# memory_mkII.net
KiCad netlist of a schematic drawn in EAGLE
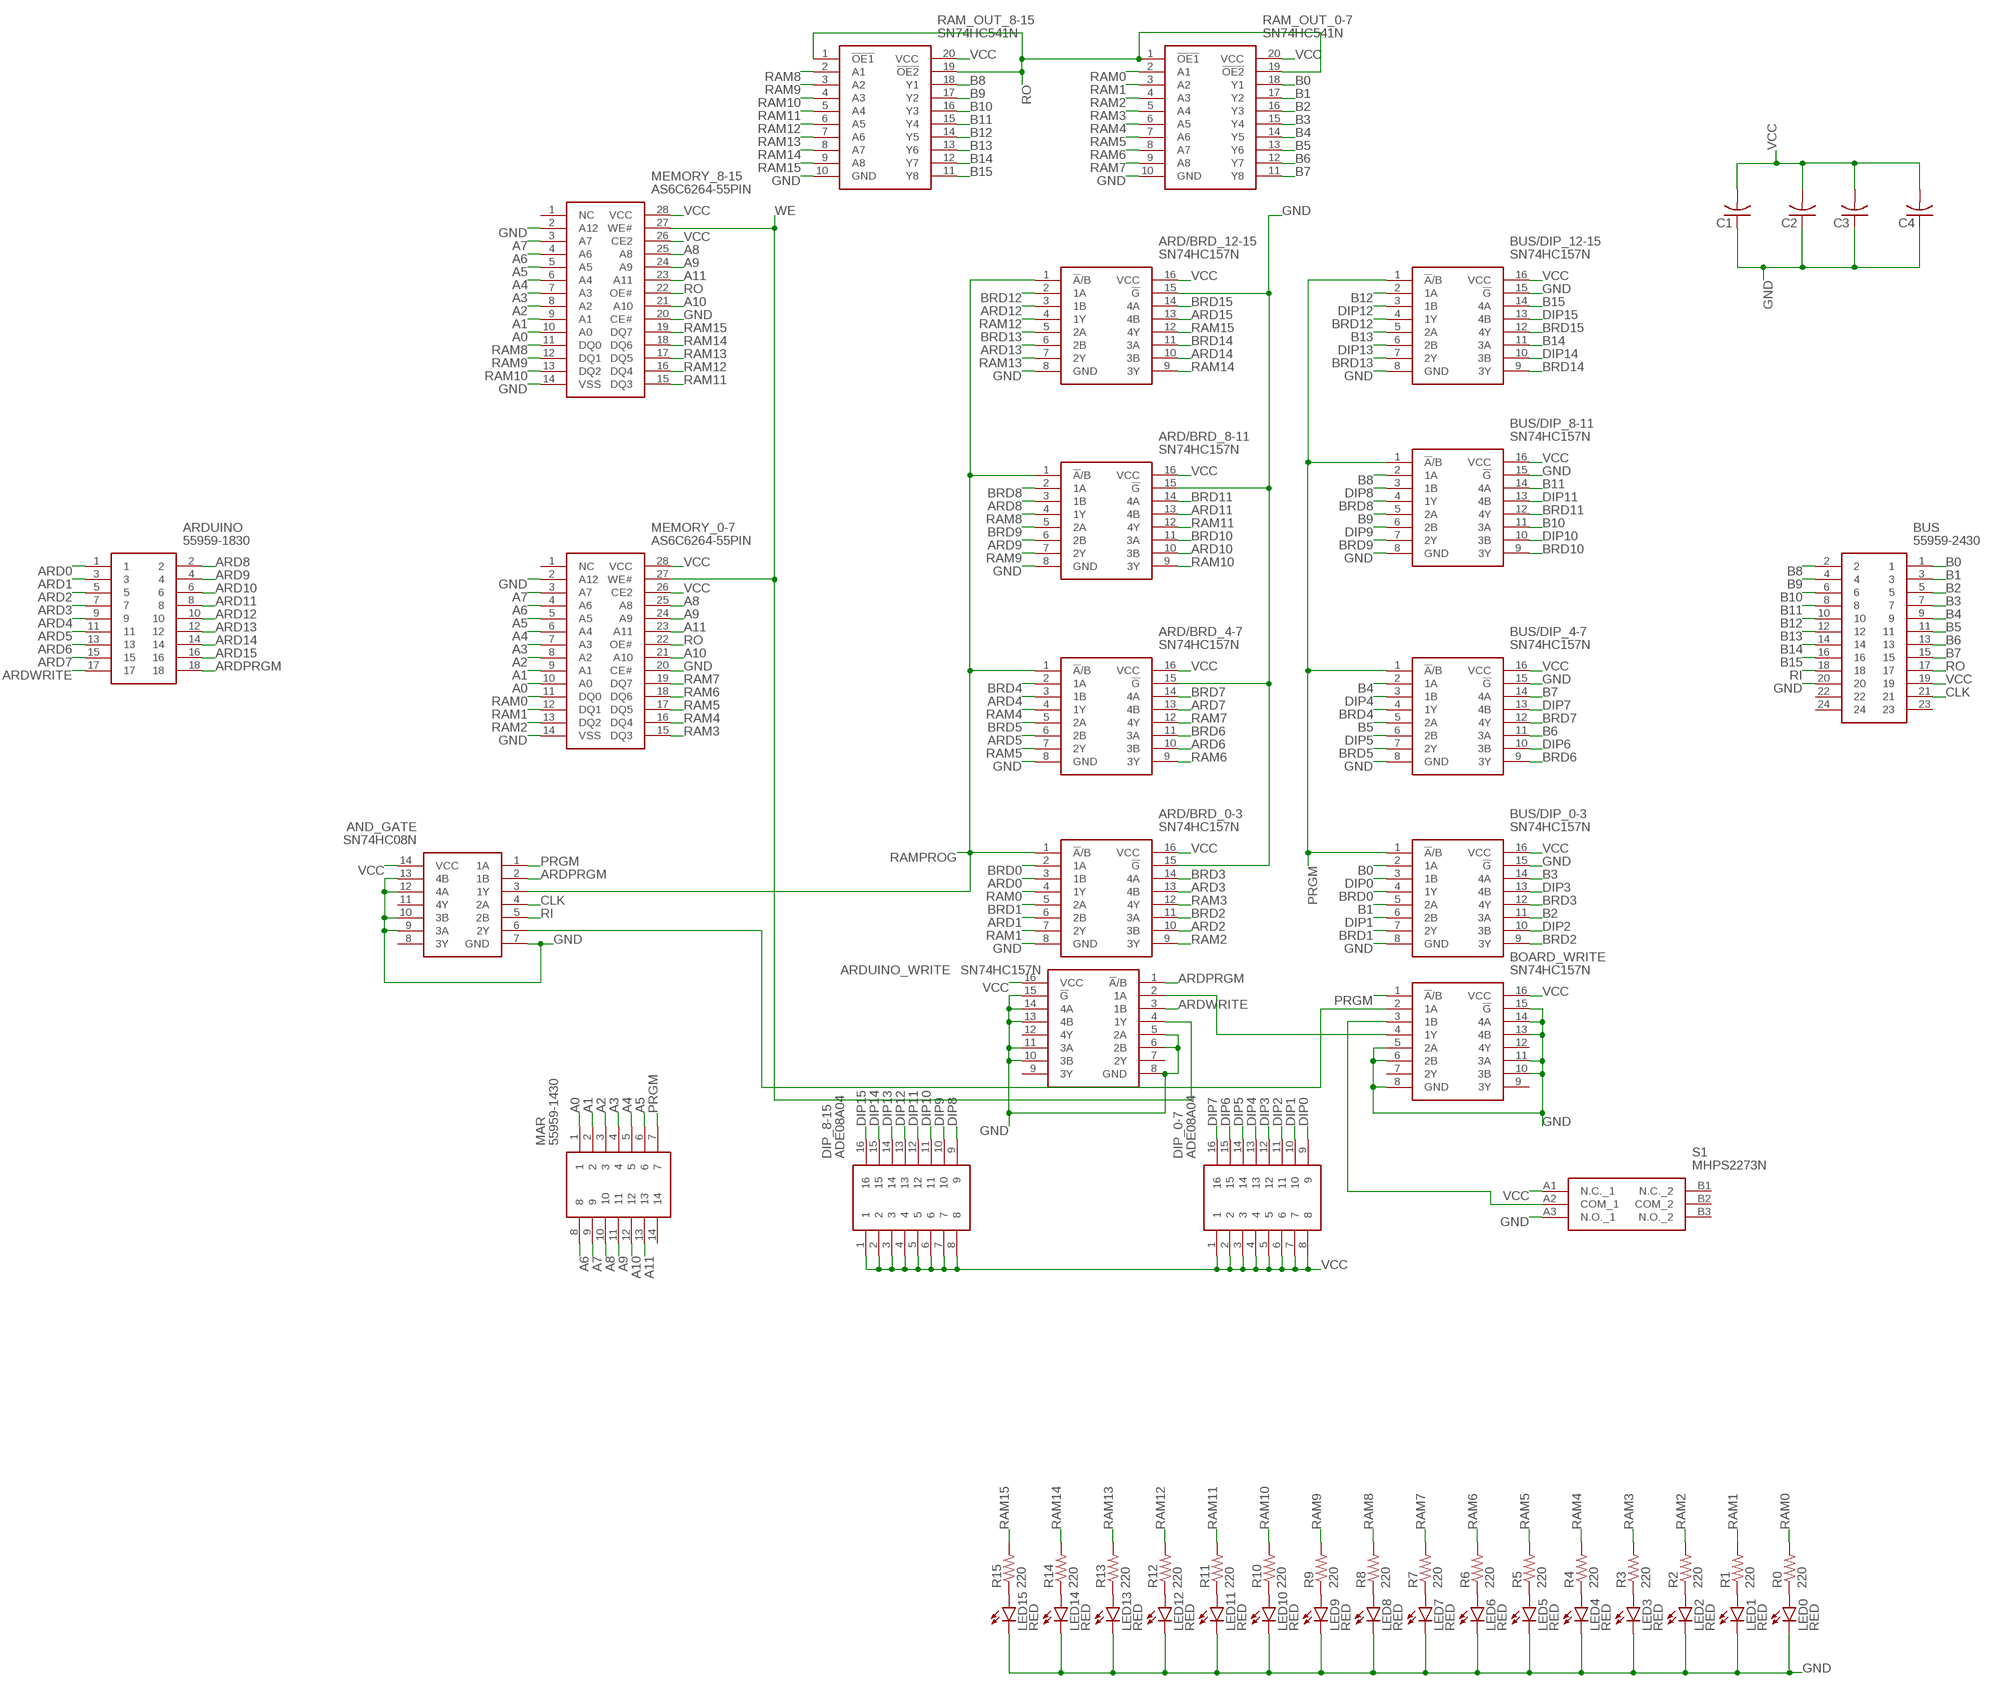
[diagram p0: schematic, sheet 1]

(export (version "E")
  (design (tool "Eeschema 10.0.6"))
  (components
    (comp (ref "AND_GATE")
      (value "SN74HC08N")
      (footprint "eagle-import:DIP794W53P254L1930H508Q14N")
      (fields (field (name "MOUSER_PART_NUMBER") "595-SN74HC08N"))
      (libsource (lib "eagle-import") (part "SN74HC08N"))
    )
    (comp (ref "ARD/BRD_0-3")
      (value "SN74HC157N")
      (footprint "eagle-import:DIP794W53P254L1930H508Q16N")
      (fields (field (name "MOUSER_PART_NUMBER") "595-SN74HC157N"))
      (libsource (lib "eagle-import") (part "SN74HC157N"))
    )
    (comp (ref "ARD/BRD_4-7")
      (value "SN74HC157N")
      (footprint "eagle-import:DIP794W53P254L1930H508Q16N")
      (fields (field (name "MOUSER_PART_NUMBER") "595-SN74HC157N"))
      (libsource (lib "eagle-import") (part "SN74HC157N"))
    )
    (comp (ref "ARD/BRD_8-11")
      (value "SN74HC157N")
      (footprint "eagle-import:DIP794W53P254L1930H508Q16N")
      (fields (field (name "MOUSER_PART_NUMBER") "595-SN74HC157N"))
      (libsource (lib "eagle-import") (part "SN74HC157N"))
    )
    (comp (ref "ARD/BRD_12-15")
      (value "SN74HC157N")
      (footprint "eagle-import:DIP794W53P254L1930H508Q16N")
      (fields (field (name "MOUSER_PART_NUMBER") "595-SN74HC157N"))
      (libsource (lib "eagle-import") (part "SN74HC157N"))
    )
    (comp (ref "ARDUINO")
      (value "55959-1830")
      (footprint "eagle-import:SHDR18W65P250X200_2X9_2140X140")
      (fields (field (name "MOUSER_PART_NUMBER") "538-55959-1830"))
      (libsource (lib "eagle-import") (part "55959-1830"))
    )
    (comp (ref "ARDUINO_WRITE")
      (value "SN74HC157N")
      (footprint "eagle-import:DIP794W53P254L1930H508Q16N")
      (fields (field (name "MOUSER_PART_NUMBER") "595-SN74HC157N"))
      (libsource (lib "eagle-import") (part "SN74HC157N"))
    )
    (comp (ref "BOARD_WRITE")
      (value "SN74HC157N")
      (footprint "eagle-import:DIP794W53P254L1930H508Q16N")
      (fields (field (name "MOUSER_PART_NUMBER") "595-SN74HC157N"))
      (libsource (lib "eagle-import") (part "SN74HC157N"))
    )
    (comp (ref "BUS")
      (value "55959-2430")
      (footprint "eagle-import:559592430")
      (fields (field (name "MOUSER_PART_NUMBER") "538-55959-2430"))
      (libsource (lib "eagle-import") (part "55959-2430"))
    )
    (comp (ref "BUS/DIP_0-3")
      (value "SN74HC157N")
      (footprint "eagle-import:DIP794W53P254L1930H508Q16N")
      (fields (field (name "MOUSER_PART_NUMBER") "595-SN74HC157N"))
      (libsource (lib "eagle-import") (part "SN74HC157N"))
    )
    (comp (ref "BUS/DIP_4-7")
      (value "SN74HC157N")
      (footprint "eagle-import:DIP794W53P254L1930H508Q16N")
      (fields (field (name "MOUSER_PART_NUMBER") "595-SN74HC157N"))
      (libsource (lib "eagle-import") (part "SN74HC157N"))
    )
    (comp (ref "BUS/DIP_8-11")
      (value "SN74HC157N")
      (footprint "eagle-import:DIP794W53P254L1930H508Q16N")
      (fields (field (name "MOUSER_PART_NUMBER") "595-SN74HC157N"))
      (libsource (lib "eagle-import") (part "SN74HC157N"))
    )
    (comp (ref "BUS/DIP_12-15")
      (value "SN74HC157N")
      (footprint "eagle-import:DIP794W53P254L1930H508Q16N")
      (fields (field (name "MOUSER_PART_NUMBER") "595-SN74HC157N"))
      (libsource (lib "eagle-import") (part "SN74HC157N"))
    )
    (comp (ref "C1")
      (value "C-US025-024X044")
      (footprint "eagle-import:C025-024X044")
      (libsource (lib "eagle-import") (part "C-US025-024X044"))
    )
    (comp (ref "C2")
      (value "C-US025-024X044")
      (footprint "eagle-import:C025-024X044")
      (libsource (lib "eagle-import") (part "C-US025-024X044"))
    )
    (comp (ref "C3")
      (value "C-US025-024X044")
      (footprint "eagle-import:C025-024X044")
      (libsource (lib "eagle-import") (part "C-US025-024X044"))
    )
    (comp (ref "C4")
      (value "C-US025-024X044")
      (footprint "eagle-import:C025-024X044")
      (libsource (lib "eagle-import") (part "C-US025-024X044"))
    )
    (comp (ref "DIP_0-7")
      (value "ADE08A04")
      (footprint "eagle-import:DIP810W60P254L2225H590Q16N")
      (fields (field (name "MOUSER_PART_NUMBER") "506-ADE08A04"))
      (libsource (lib "eagle-import") (part "ADE08A04"))
    )
    (comp (ref "DIP_8-15")
      (value "ADE08A04")
      (footprint "eagle-import:DIP810W60P254L2225H590Q16N")
      (fields (field (name "MOUSER_PART_NUMBER") "506-ADE08A04"))
      (libsource (lib "eagle-import") (part "ADE08A04"))
    )
    (comp (ref "LED0")
      (value "RED")
      (footprint "eagle-import:LED3MM")
      (libsource (lib "eagle-import") (part "LED3MM"))
    )
    (comp (ref "LED1")
      (value "RED")
      (footprint "eagle-import:LED3MM")
      (libsource (lib "eagle-import") (part "LED3MM"))
    )
    (comp (ref "LED2")
      (value "RED")
      (footprint "eagle-import:LED3MM")
      (libsource (lib "eagle-import") (part "LED3MM"))
    )
    (comp (ref "LED3")
      (value "RED")
      (footprint "eagle-import:LED3MM")
      (libsource (lib "eagle-import") (part "LED3MM"))
    )
    (comp (ref "LED4")
      (value "RED")
      (footprint "eagle-import:LED3MM")
      (libsource (lib "eagle-import") (part "LED3MM"))
    )
    (comp (ref "LED5")
      (value "RED")
      (footprint "eagle-import:LED3MM")
      (libsource (lib "eagle-import") (part "LED3MM"))
    )
    (comp (ref "LED6")
      (value "RED")
      (footprint "eagle-import:LED3MM")
      (libsource (lib "eagle-import") (part "LED3MM"))
    )
    (comp (ref "LED7")
      (value "RED")
      (footprint "eagle-import:LED3MM")
      (libsource (lib "eagle-import") (part "LED3MM"))
    )
    (comp (ref "LED8")
      (value "RED")
      (footprint "eagle-import:LED3MM")
      (libsource (lib "eagle-import") (part "LED3MM"))
    )
    (comp (ref "LED9")
      (value "RED")
      (footprint "eagle-import:LED3MM")
      (libsource (lib "eagle-import") (part "LED3MM"))
    )
    (comp (ref "LED10")
      (value "RED")
      (footprint "eagle-import:LED3MM")
      (libsource (lib "eagle-import") (part "LED3MM"))
    )
    (comp (ref "LED11")
      (value "RED")
      (footprint "eagle-import:LED3MM")
      (libsource (lib "eagle-import") (part "LED3MM"))
    )
    (comp (ref "LED12")
      (value "RED")
      (footprint "eagle-import:LED3MM")
      (libsource (lib "eagle-import") (part "LED3MM"))
    )
    (comp (ref "LED13")
      (value "RED")
      (footprint "eagle-import:LED3MM")
      (libsource (lib "eagle-import") (part "LED3MM"))
    )
    (comp (ref "LED14")
      (value "RED")
      (footprint "eagle-import:LED3MM")
      (libsource (lib "eagle-import") (part "LED3MM"))
    )
    (comp (ref "LED15")
      (value "RED")
      (footprint "eagle-import:LED3MM")
      (libsource (lib "eagle-import") (part "LED3MM"))
    )
    (comp (ref "MAR")
      (value "55959-1430")
      (footprint "eagle-import:559591430")
      (fields (field (name "MOUSER_PART_NUMBER") "538-55959-1430"))
      (libsource (lib "eagle-import") (part "55959-1430"))
    )
    (comp (ref "MEMORY_0-7")
      (value "AS6C6264-55PIN")
      (footprint "eagle-import:DIP1524W51P254L3632H394Q28N")
      (fields (field (name "MOUSER_PART_NUMBER") "913-AS6C6264-55PIN"))
      (libsource (lib "eagle-import") (part "AS6C6264-55PIN"))
    )
    (comp (ref "MEMORY_8-15")
      (value "AS6C6264-55PIN")
      (footprint "eagle-import:DIP1524W51P254L3632H394Q28N")
      (fields (field (name "MOUSER_PART_NUMBER") "913-AS6C6264-55PIN"))
      (libsource (lib "eagle-import") (part "AS6C6264-55PIN"))
    )
    (comp (ref "R0")
      (value "220")
      (footprint "eagle-import:0204_7")
      (libsource (lib "eagle-import") (part "R-US_0204/7"))
    )
    (comp (ref "R1")
      (value "220")
      (footprint "eagle-import:0204_7")
      (libsource (lib "eagle-import") (part "R-US_0204/7"))
    )
    (comp (ref "R2")
      (value "220")
      (footprint "eagle-import:0204_7")
      (libsource (lib "eagle-import") (part "R-US_0204/7"))
    )
    (comp (ref "R3")
      (value "220")
      (footprint "eagle-import:0204_7")
      (libsource (lib "eagle-import") (part "R-US_0204/7"))
    )
    (comp (ref "R4")
      (value "220")
      (footprint "eagle-import:0204_7")
      (libsource (lib "eagle-import") (part "R-US_0204/7"))
    )
    (comp (ref "R5")
      (value "220")
      (footprint "eagle-import:0204_7")
      (libsource (lib "eagle-import") (part "R-US_0204/7"))
    )
    (comp (ref "R6")
      (value "220")
      (footprint "eagle-import:0204_7")
      (libsource (lib "eagle-import") (part "R-US_0204/7"))
    )
    (comp (ref "R7")
      (value "220")
      (footprint "eagle-import:0204_7")
      (libsource (lib "eagle-import") (part "R-US_0204/7"))
    )
    (comp (ref "R8")
      (value "220")
      (footprint "eagle-import:0204_7")
      (libsource (lib "eagle-import") (part "R-US_0204/7"))
    )
    (comp (ref "R9")
      (value "220")
      (footprint "eagle-import:0204_7")
      (libsource (lib "eagle-import") (part "R-US_0204/7"))
    )
    (comp (ref "R10")
      (value "220")
      (footprint "eagle-import:0204_7")
      (libsource (lib "eagle-import") (part "R-US_0204/7"))
    )
    (comp (ref "R11")
      (value "220")
      (footprint "eagle-import:0204_7")
      (libsource (lib "eagle-import") (part "R-US_0204/7"))
    )
    (comp (ref "R12")
      (value "220")
      (footprint "eagle-import:0204_7")
      (libsource (lib "eagle-import") (part "R-US_0204/7"))
    )
    (comp (ref "R13")
      (value "220")
      (footprint "eagle-import:0204_7")
      (libsource (lib "eagle-import") (part "R-US_0204/7"))
    )
    (comp (ref "R14")
      (value "220")
      (footprint "eagle-import:0204_7")
      (libsource (lib "eagle-import") (part "R-US_0204/7"))
    )
    (comp (ref "R15")
      (value "220")
      (footprint "eagle-import:0204_7")
      (libsource (lib "eagle-import") (part "R-US_0204/7"))
    )
    (comp (ref "RAM_OUT_0-7")
      (value "SN74HC541N")
      (footprint "eagle-import:DIP794W53P254L2540H508Q20N")
      (fields (field (name "MOUSER_PART_NUMBER") "595-SN74HC541N"))
      (libsource (lib "eagle-import") (part "SN74HC541N"))
    )
    (comp (ref "RAM_OUT_8-15")
      (value "SN74HC541N")
      (footprint "eagle-import:DIP794W53P254L2540H508Q20N")
      (fields (field (name "MOUSER_PART_NUMBER") "595-SN74HC541N"))
      (libsource (lib "eagle-import") (part "SN74HC541N"))
    )
    (comp (ref "S1")
      (value "MHPS2273N")
      (footprint "eagle-import:MHPS2273N")
      (fields (field (name "MOUSER_PART_NUMBER") "642-MHPS2273N"))
      (libsource (lib "eagle-import") (part "MHPS2273N"))
    )
  )
  (nets
    (net (code "1") (name "/A0") (class "Default")
      (node (ref "MAR") (pin "1") (pinfunction "1_1") (pintype "bidirectional"))
      (node (ref "MEMORY_0-7") (pin "10") (pinfunction "A0_10") (pintype "bidirectional"))
      (node (ref "MEMORY_8-15") (pin "10") (pinfunction "A0_10") (pintype "bidirectional"))
    )
    (net (code "2") (name "/A1") (class "Default")
      (node (ref "MAR") (pin "2") (pinfunction "2_2") (pintype "bidirectional"))
      (node (ref "MEMORY_0-7") (pin "9") (pinfunction "A1_9") (pintype "bidirectional"))
      (node (ref "MEMORY_8-15") (pin "9") (pinfunction "A1_9") (pintype "bidirectional"))
    )
    (net (code "3") (name "/A2") (class "Default")
      (node (ref "MAR") (pin "3") (pinfunction "3_3") (pintype "bidirectional"))
      (node (ref "MEMORY_0-7") (pin "8") (pinfunction "A2_8") (pintype "bidirectional"))
      (node (ref "MEMORY_8-15") (pin "8") (pinfunction "A2_8") (pintype "bidirectional"))
    )
    (net (code "4") (name "/A3") (class "Default")
      (node (ref "MAR") (pin "4") (pinfunction "4_4") (pintype "bidirectional"))
      (node (ref "MEMORY_0-7") (pin "7") (pinfunction "A3_7") (pintype "bidirectional"))
      (node (ref "MEMORY_8-15") (pin "7") (pinfunction "A3_7") (pintype "bidirectional"))
    )
    (net (code "5") (name "/A4") (class "Default")
      (node (ref "MAR") (pin "5") (pinfunction "5_5") (pintype "bidirectional"))
      (node (ref "MEMORY_0-7") (pin "6") (pinfunction "A4_6") (pintype "bidirectional"))
      (node (ref "MEMORY_8-15") (pin "6") (pinfunction "A4_6") (pintype "bidirectional"))
    )
    (net (code "6") (name "/A5") (class "Default")
      (node (ref "MAR") (pin "6") (pinfunction "6_6") (pintype "bidirectional"))
      (node (ref "MEMORY_0-7") (pin "5") (pinfunction "A5_5") (pintype "bidirectional"))
      (node (ref "MEMORY_8-15") (pin "5") (pinfunction "A5_5") (pintype "bidirectional"))
    )
    (net (code "7") (name "/A6") (class "Default")
      (node (ref "MAR") (pin "8") (pinfunction "8_8") (pintype "bidirectional"))
      (node (ref "MEMORY_0-7") (pin "4") (pinfunction "A6_4") (pintype "bidirectional"))
      (node (ref "MEMORY_8-15") (pin "4") (pinfunction "A6_4") (pintype "bidirectional"))
    )
    (net (code "8") (name "/A7") (class "Default")
      (node (ref "MAR") (pin "9") (pinfunction "9_9") (pintype "bidirectional"))
      (node (ref "MEMORY_0-7") (pin "3") (pinfunction "A7_3") (pintype "bidirectional"))
      (node (ref "MEMORY_8-15") (pin "3") (pinfunction "A7_3") (pintype "bidirectional"))
    )
    (net (code "9") (name "/A8") (class "Default")
      (node (ref "MAR") (pin "10") (pinfunction "10_10") (pintype "bidirectional"))
      (node (ref "MEMORY_0-7") (pin "25") (pinfunction "A8_25") (pintype "bidirectional"))
      (node (ref "MEMORY_8-15") (pin "25") (pinfunction "A8_25") (pintype "bidirectional"))
    )
    (net (code "10") (name "/A9") (class "Default")
      (node (ref "MAR") (pin "11") (pinfunction "11_11") (pintype "bidirectional"))
      (node (ref "MEMORY_0-7") (pin "24") (pinfunction "A9_24") (pintype "bidirectional"))
      (node (ref "MEMORY_8-15") (pin "24") (pinfunction "A9_24") (pintype "bidirectional"))
    )
    (net (code "11") (name "/A10") (class "Default")
      (node (ref "MAR") (pin "12") (pinfunction "12_12") (pintype "bidirectional"))
      (node (ref "MEMORY_0-7") (pin "21") (pinfunction "A10_21") (pintype "bidirectional"))
      (node (ref "MEMORY_8-15") (pin "21") (pinfunction "A10_21") (pintype "bidirectional"))
    )
    (net (code "12") (name "/A11") (class "Default")
      (node (ref "MAR") (pin "13") (pinfunction "13_13") (pintype "bidirectional"))
      (node (ref "MEMORY_0-7") (pin "23") (pinfunction "A11_23") (pintype "bidirectional"))
      (node (ref "MEMORY_8-15") (pin "23") (pinfunction "A11_23") (pintype "bidirectional"))
    )
    (net (code "13") (name "/ARD0") (class "Default")
      (node (ref "ARD/BRD_0-3") (pin "3") (pinfunction "1B_3") (pintype "bidirectional"))
      (node (ref "ARDUINO") (pin "1") (pinfunction "1_1") (pintype "bidirectional"))
    )
    (net (code "14") (name "/ARD1") (class "Default")
      (node (ref "ARD/BRD_0-3") (pin "6") (pinfunction "2B_6") (pintype "bidirectional"))
      (node (ref "ARDUINO") (pin "3") (pinfunction "3_3") (pintype "bidirectional"))
    )
    (net (code "15") (name "/ARD2") (class "Default")
      (node (ref "ARD/BRD_0-3") (pin "10") (pinfunction "3B_10") (pintype "bidirectional"))
      (node (ref "ARDUINO") (pin "5") (pinfunction "5_5") (pintype "bidirectional"))
    )
    (net (code "16") (name "/ARD3") (class "Default")
      (node (ref "ARD/BRD_0-3") (pin "13") (pinfunction "4B_13") (pintype "bidirectional"))
      (node (ref "ARDUINO") (pin "7") (pinfunction "7_7") (pintype "bidirectional"))
    )
    (net (code "17") (name "/ARD4") (class "Default")
      (node (ref "ARD/BRD_4-7") (pin "3") (pinfunction "1B_3") (pintype "bidirectional"))
      (node (ref "ARDUINO") (pin "9") (pinfunction "9_9") (pintype "bidirectional"))
    )
    (net (code "18") (name "/ARD5") (class "Default")
      (node (ref "ARD/BRD_4-7") (pin "6") (pinfunction "2B_6") (pintype "bidirectional"))
      (node (ref "ARDUINO") (pin "11") (pinfunction "11_11") (pintype "bidirectional"))
    )
    (net (code "19") (name "/ARD6") (class "Default")
      (node (ref "ARD/BRD_4-7") (pin "10") (pinfunction "3B_10") (pintype "bidirectional"))
      (node (ref "ARDUINO") (pin "13") (pinfunction "13_13") (pintype "bidirectional"))
    )
    (net (code "20") (name "/ARD7") (class "Default")
      (node (ref "ARD/BRD_4-7") (pin "13") (pinfunction "4B_13") (pintype "bidirectional"))
      (node (ref "ARDUINO") (pin "15") (pinfunction "15_15") (pintype "bidirectional"))
    )
    (net (code "21") (name "/ARD8") (class "Default")
      (node (ref "ARD/BRD_8-11") (pin "3") (pinfunction "1B_3") (pintype "bidirectional"))
      (node (ref "ARDUINO") (pin "2") (pinfunction "2_2") (pintype "bidirectional"))
    )
    (net (code "22") (name "/ARD9") (class "Default")
      (node (ref "ARD/BRD_8-11") (pin "6") (pinfunction "2B_6") (pintype "bidirectional"))
      (node (ref "ARDUINO") (pin "4") (pinfunction "4_4") (pintype "bidirectional"))
    )
    (net (code "23") (name "/ARD10") (class "Default")
      (node (ref "ARD/BRD_8-11") (pin "10") (pinfunction "3B_10") (pintype "bidirectional"))
      (node (ref "ARDUINO") (pin "6") (pinfunction "6_6") (pintype "bidirectional"))
    )
    (net (code "24") (name "/ARD11") (class "Default")
      (node (ref "ARD/BRD_8-11") (pin "13") (pinfunction "4B_13") (pintype "bidirectional"))
      (node (ref "ARDUINO") (pin "8") (pinfunction "8_8") (pintype "bidirectional"))
    )
    (net (code "25") (name "/ARD12") (class "Default")
      (node (ref "ARD/BRD_12-15") (pin "3") (pinfunction "1B_3") (pintype "bidirectional"))
      (node (ref "ARDUINO") (pin "10") (pinfunction "10_10") (pintype "bidirectional"))
    )
    (net (code "26") (name "/ARD13") (class "Default")
      (node (ref "ARD/BRD_12-15") (pin "6") (pinfunction "2B_6") (pintype "bidirectional"))
      (node (ref "ARDUINO") (pin "12") (pinfunction "12_12") (pintype "bidirectional"))
    )
    (net (code "27") (name "/ARD14") (class "Default")
      (node (ref "ARD/BRD_12-15") (pin "10") (pinfunction "3B_10") (pintype "bidirectional"))
      (node (ref "ARDUINO") (pin "14") (pinfunction "14_14") (pintype "bidirectional"))
    )
    (net (code "28") (name "/ARD15") (class "Default")
      (node (ref "ARD/BRD_12-15") (pin "13") (pinfunction "4B_13") (pintype "bidirectional"))
      (node (ref "ARDUINO") (pin "16") (pinfunction "16_16") (pintype "bidirectional"))
    )
    (net (code "29") (name "/ARDPRGM") (class "Default")
      (node (ref "AND_GATE") (pin "2") (pinfunction "1B_2") (pintype "bidirectional"))
      (node (ref "ARDUINO") (pin "18") (pinfunction "18_18") (pintype "bidirectional"))
      (node (ref "ARDUINO_WRITE") (pin "1") (pinfunction "~{A}/B_1") (pintype "bidirectional"))
    )
    (net (code "30") (name "/ARDWRITE") (class "Default")
      (node (ref "ARDUINO") (pin "17") (pinfunction "17_17") (pintype "bidirectional"))
      (node (ref "ARDUINO_WRITE") (pin "3") (pinfunction "1B_3") (pintype "bidirectional"))
    )
    (net (code "31") (name "/B0") (class "Default")
      (node (ref "BUS") (pin "1") (pinfunction "1_1") (pintype "bidirectional"))
      (node (ref "BUS/DIP_0-3") (pin "2") (pinfunction "1A_2") (pintype "bidirectional"))
      (node (ref "RAM_OUT_0-7") (pin "18") (pinfunction "Y1_18") (pintype "bidirectional"))
    )
    (net (code "32") (name "/B1") (class "Default")
      (node (ref "BUS") (pin "3") (pinfunction "3_3") (pintype "bidirectional"))
      (node (ref "BUS/DIP_0-3") (pin "5") (pinfunction "2A_5") (pintype "bidirectional"))
      (node (ref "RAM_OUT_0-7") (pin "17") (pinfunction "Y2_17") (pintype "bidirectional"))
    )
    (net (code "33") (name "/B2") (class "Default")
      (node (ref "BUS") (pin "5") (pinfunction "5_5") (pintype "bidirectional"))
      (node (ref "BUS/DIP_0-3") (pin "11") (pinfunction "3A_11") (pintype "bidirectional"))
      (node (ref "RAM_OUT_0-7") (pin "16") (pinfunction "Y3_16") (pintype "bidirectional"))
    )
    (net (code "34") (name "/B3") (class "Default")
      (node (ref "BUS") (pin "7") (pinfunction "7_7") (pintype "bidirectional"))
      (node (ref "BUS/DIP_0-3") (pin "14") (pinfunction "4A_14") (pintype "bidirectional"))
      (node (ref "RAM_OUT_0-7") (pin "15") (pinfunction "Y4_15") (pintype "bidirectional"))
    )
    (net (code "35") (name "/B4") (class "Default")
      (node (ref "BUS") (pin "9") (pinfunction "9_9") (pintype "bidirectional"))
      (node (ref "BUS/DIP_4-7") (pin "2") (pinfunction "1A_2") (pintype "bidirectional"))
      (node (ref "RAM_OUT_0-7") (pin "14") (pinfunction "Y5_14") (pintype "bidirectional"))
    )
    (net (code "36") (name "/B5") (class "Default")
      (node (ref "BUS") (pin "11") (pinfunction "11_11") (pintype "bidirectional"))
      (node (ref "BUS/DIP_4-7") (pin "5") (pinfunction "2A_5") (pintype "bidirectional"))
      (node (ref "RAM_OUT_0-7") (pin "13") (pinfunction "Y6_13") (pintype "bidirectional"))
    )
    (net (code "37") (name "/B6") (class "Default")
      (node (ref "BUS") (pin "13") (pinfunction "13_13") (pintype "bidirectional"))
      (node (ref "BUS/DIP_4-7") (pin "11") (pinfunction "3A_11") (pintype "bidirectional"))
      (node (ref "RAM_OUT_0-7") (pin "12") (pinfunction "Y7_12") (pintype "bidirectional"))
    )
    (net (code "38") (name "/B7") (class "Default")
      (node (ref "BUS") (pin "15") (pinfunction "15_15") (pintype "bidirectional"))
      (node (ref "BUS/DIP_4-7") (pin "14") (pinfunction "4A_14") (pintype "bidirectional"))
      (node (ref "RAM_OUT_0-7") (pin "11") (pinfunction "Y8_11") (pintype "bidirectional"))
    )
    (net (code "39") (name "/B8") (class "Default")
      (node (ref "BUS") (pin "2") (pinfunction "2_2") (pintype "bidirectional"))
      (node (ref "BUS/DIP_8-11") (pin "2") (pinfunction "1A_2") (pintype "bidirectional"))
      (node (ref "RAM_OUT_8-15") (pin "18") (pinfunction "Y1_18") (pintype "bidirectional"))
    )
    (net (code "40") (name "/B9") (class "Default")
      (node (ref "BUS") (pin "4") (pinfunction "4_4") (pintype "bidirectional"))
      (node (ref "BUS/DIP_8-11") (pin "5") (pinfunction "2A_5") (pintype "bidirectional"))
      (node (ref "RAM_OUT_8-15") (pin "17") (pinfunction "Y2_17") (pintype "bidirectional"))
    )
    (net (code "41") (name "/B10") (class "Default")
      (node (ref "BUS") (pin "6") (pinfunction "6_6") (pintype "bidirectional"))
      (node (ref "BUS/DIP_8-11") (pin "11") (pinfunction "3A_11") (pintype "bidirectional"))
      (node (ref "RAM_OUT_8-15") (pin "16") (pinfunction "Y3_16") (pintype "bidirectional"))
    )
    (net (code "42") (name "/B11") (class "Default")
      (node (ref "BUS") (pin "8") (pinfunction "8_8") (pintype "bidirectional"))
      (node (ref "BUS/DIP_8-11") (pin "14") (pinfunction "4A_14") (pintype "bidirectional"))
      (node (ref "RAM_OUT_8-15") (pin "15") (pinfunction "Y4_15") (pintype "bidirectional"))
    )
    (net (code "43") (name "/B12") (class "Default")
      (node (ref "BUS") (pin "10") (pinfunction "10_10") (pintype "bidirectional"))
      (node (ref "BUS/DIP_12-15") (pin "2") (pinfunction "1A_2") (pintype "bidirectional"))
      (node (ref "RAM_OUT_8-15") (pin "14") (pinfunction "Y5_14") (pintype "bidirectional"))
    )
    (net (code "44") (name "/B13") (class "Default")
      (node (ref "BUS") (pin "12") (pinfunction "12_12") (pintype "bidirectional"))
      (node (ref "BUS/DIP_12-15") (pin "5") (pinfunction "2A_5") (pintype "bidirectional"))
      (node (ref "RAM_OUT_8-15") (pin "13") (pinfunction "Y6_13") (pintype "bidirectional"))
    )
    (net (code "45") (name "/B14") (class "Default")
      (node (ref "BUS") (pin "14") (pinfunction "14_14") (pintype "bidirectional"))
      (node (ref "BUS/DIP_12-15") (pin "11") (pinfunction "3A_11") (pintype "bidirectional"))
      (node (ref "RAM_OUT_8-15") (pin "12") (pinfunction "Y7_12") (pintype "bidirectional"))
    )
    (net (code "46") (name "/B15") (class "Default")
      (node (ref "BUS") (pin "16") (pinfunction "16_16") (pintype "bidirectional"))
      (node (ref "BUS/DIP_12-15") (pin "14") (pinfunction "4A_14") (pintype "bidirectional"))
      (node (ref "RAM_OUT_8-15") (pin "11") (pinfunction "Y8_11") (pintype "bidirectional"))
    )
    (net (code "47") (name "/BRD0") (class "Default")
      (node (ref "ARD/BRD_0-3") (pin "2") (pinfunction "1A_2") (pintype "bidirectional"))
      (node (ref "BUS/DIP_0-3") (pin "4") (pinfunction "1Y_4") (pintype "bidirectional"))
    )
    (net (code "48") (name "/BRD1") (class "Default")
      (node (ref "ARD/BRD_0-3") (pin "5") (pinfunction "2A_5") (pintype "bidirectional"))
      (node (ref "BUS/DIP_0-3") (pin "7") (pinfunction "2Y_7") (pintype "bidirectional"))
    )
    (net (code "49") (name "/BRD2") (class "Default")
      (node (ref "ARD/BRD_0-3") (pin "11") (pinfunction "3A_11") (pintype "bidirectional"))
      (node (ref "BUS/DIP_0-3") (pin "9") (pinfunction "3Y_9") (pintype "bidirectional"))
    )
    (net (code "50") (name "/BRD3") (class "Default")
      (node (ref "ARD/BRD_0-3") (pin "14") (pinfunction "4A_14") (pintype "bidirectional"))
      (node (ref "BUS/DIP_0-3") (pin "12") (pinfunction "4Y_12") (pintype "bidirectional"))
    )
    (net (code "51") (name "/BRD4") (class "Default")
      (node (ref "ARD/BRD_4-7") (pin "2") (pinfunction "1A_2") (pintype "bidirectional"))
      (node (ref "BUS/DIP_4-7") (pin "4") (pinfunction "1Y_4") (pintype "bidirectional"))
    )
    (net (code "52") (name "/BRD5") (class "Default")
      (node (ref "ARD/BRD_4-7") (pin "5") (pinfunction "2A_5") (pintype "bidirectional"))
      (node (ref "BUS/DIP_4-7") (pin "7") (pinfunction "2Y_7") (pintype "bidirectional"))
    )
    (net (code "53") (name "/BRD6") (class "Default")
      (node (ref "ARD/BRD_4-7") (pin "11") (pinfunction "3A_11") (pintype "bidirectional"))
      (node (ref "BUS/DIP_4-7") (pin "9") (pinfunction "3Y_9") (pintype "bidirectional"))
    )
    (net (code "54") (name "/BRD7") (class "Default")
      (node (ref "ARD/BRD_4-7") (pin "14") (pinfunction "4A_14") (pintype "bidirectional"))
      (node (ref "BUS/DIP_4-7") (pin "12") (pinfunction "4Y_12") (pintype "bidirectional"))
    )
    (net (code "55") (name "/BRD8") (class "Default")
      (node (ref "ARD/BRD_8-11") (pin "2") (pinfunction "1A_2") (pintype "bidirectional"))
      (node (ref "BUS/DIP_8-11") (pin "4") (pinfunction "1Y_4") (pintype "bidirectional"))
    )
    (net (code "56") (name "/BRD9") (class "Default")
      (node (ref "ARD/BRD_8-11") (pin "5") (pinfunction "2A_5") (pintype "bidirectional"))
      (node (ref "BUS/DIP_8-11") (pin "7") (pinfunction "2Y_7") (pintype "bidirectional"))
    )
    (net (code "57") (name "/BRD10") (class "Default")
      (node (ref "ARD/BRD_8-11") (pin "11") (pinfunction "3A_11") (pintype "bidirectional"))
      (node (ref "BUS/DIP_8-11") (pin "9") (pinfunction "3Y_9") (pintype "bidirectional"))
    )
    (net (code "58") (name "/BRD11") (class "Default")
      (node (ref "ARD/BRD_8-11") (pin "14") (pinfunction "4A_14") (pintype "bidirectional"))
      (node (ref "BUS/DIP_8-11") (pin "12") (pinfunction "4Y_12") (pintype "bidirectional"))
    )
    (net (code "59") (name "/BRD12") (class "Default")
      (node (ref "ARD/BRD_12-15") (pin "2") (pinfunction "1A_2") (pintype "bidirectional"))
      (node (ref "BUS/DIP_12-15") (pin "4") (pinfunction "1Y_4") (pintype "bidirectional"))
    )
    (net (code "60") (name "/BRD13") (class "Default")
      (node (ref "ARD/BRD_12-15") (pin "5") (pinfunction "2A_5") (pintype "bidirectional"))
      (node (ref "BUS/DIP_12-15") (pin "7") (pinfunction "2Y_7") (pintype "bidirectional"))
    )
    (net (code "61") (name "/BRD14") (class "Default")
      (node (ref "ARD/BRD_12-15") (pin "11") (pinfunction "3A_11") (pintype "bidirectional"))
      (node (ref "BUS/DIP_12-15") (pin "9") (pinfunction "3Y_9") (pintype "bidirectional"))
    )
    (net (code "62") (name "/BRD15") (class "Default")
      (node (ref "ARD/BRD_12-15") (pin "14") (pinfunction "4A_14") (pintype "bidirectional"))
      (node (ref "BUS/DIP_12-15") (pin "12") (pinfunction "4Y_12") (pintype "bidirectional"))
    )
    (net (code "63") (name "/CLK") (class "Default")
      (node (ref "AND_GATE") (pin "4") (pinfunction "2A_4") (pintype "bidirectional"))
      (node (ref "BUS") (pin "21") (pinfunction "21_21") (pintype "bidirectional"))
    )
    (net (code "64") (name "/DIP0") (class "Default")
      (node (ref "BUS/DIP_0-3") (pin "3") (pinfunction "1B_3") (pintype "bidirectional"))
      (node (ref "DIP_0-7") (pin "9") (pinfunction "9_9") (pintype "bidirectional"))
    )
    (net (code "65") (name "/DIP1") (class "Default")
      (node (ref "BUS/DIP_0-3") (pin "6") (pinfunction "2B_6") (pintype "bidirectional"))
      (node (ref "DIP_0-7") (pin "10") (pinfunction "10_10") (pintype "bidirectional"))
    )
    (net (code "66") (name "/DIP2") (class "Default")
      (node (ref "BUS/DIP_0-3") (pin "10") (pinfunction "3B_10") (pintype "bidirectional"))
      (node (ref "DIP_0-7") (pin "11") (pinfunction "11_11") (pintype "bidirectional"))
    )
    (net (code "67") (name "/DIP3") (class "Default")
      (node (ref "BUS/DIP_0-3") (pin "13") (pinfunction "4B_13") (pintype "bidirectional"))
      (node (ref "DIP_0-7") (pin "12") (pinfunction "12_12") (pintype "bidirectional"))
    )
    (net (code "68") (name "/DIP4") (class "Default")
      (node (ref "BUS/DIP_4-7") (pin "3") (pinfunction "1B_3") (pintype "bidirectional"))
      (node (ref "DIP_0-7") (pin "13") (pinfunction "13_13") (pintype "bidirectional"))
    )
    (net (code "69") (name "/DIP5") (class "Default")
      (node (ref "BUS/DIP_4-7") (pin "6") (pinfunction "2B_6") (pintype "bidirectional"))
      (node (ref "DIP_0-7") (pin "14") (pinfunction "14_14") (pintype "bidirectional"))
    )
    (net (code "70") (name "/DIP6") (class "Default")
      (node (ref "BUS/DIP_4-7") (pin "10") (pinfunction "3B_10") (pintype "bidirectional"))
      (node (ref "DIP_0-7") (pin "15") (pinfunction "15_15") (pintype "bidirectional"))
    )
    (net (code "71") (name "/DIP7") (class "Default")
      (node (ref "BUS/DIP_4-7") (pin "13") (pinfunction "4B_13") (pintype "bidirectional"))
      (node (ref "DIP_0-7") (pin "16") (pinfunction "16_16") (pintype "bidirectional"))
    )
    (net (code "72") (name "/DIP8") (class "Default")
      (node (ref "BUS/DIP_8-11") (pin "3") (pinfunction "1B_3") (pintype "bidirectional"))
      (node (ref "DIP_8-15") (pin "9") (pinfunction "9_9") (pintype "bidirectional"))
    )
    (net (code "73") (name "/DIP9") (class "Default")
      (node (ref "BUS/DIP_8-11") (pin "6") (pinfunction "2B_6") (pintype "bidirectional"))
      (node (ref "DIP_8-15") (pin "10") (pinfunction "10_10") (pintype "bidirectional"))
    )
    (net (code "74") (name "/DIP10") (class "Default")
      (node (ref "BUS/DIP_8-11") (pin "10") (pinfunction "3B_10") (pintype "bidirectional"))
      (node (ref "DIP_8-15") (pin "11") (pinfunction "11_11") (pintype "bidirectional"))
    )
    (net (code "75") (name "/DIP11") (class "Default")
      (node (ref "BUS/DIP_8-11") (pin "13") (pinfunction "4B_13") (pintype "bidirectional"))
      (node (ref "DIP_8-15") (pin "12") (pinfunction "12_12") (pintype "bidirectional"))
    )
    (net (code "76") (name "/DIP12") (class "Default")
      (node (ref "BUS/DIP_12-15") (pin "3") (pinfunction "1B_3") (pintype "bidirectional"))
      (node (ref "DIP_8-15") (pin "13") (pinfunction "13_13") (pintype "bidirectional"))
    )
    (net (code "77") (name "/DIP13") (class "Default")
      (node (ref "BUS/DIP_12-15") (pin "6") (pinfunction "2B_6") (pintype "bidirectional"))
      (node (ref "DIP_8-15") (pin "14") (pinfunction "14_14") (pintype "bidirectional"))
    )
    (net (code "78") (name "/DIP14") (class "Default")
      (node (ref "BUS/DIP_12-15") (pin "10") (pinfunction "3B_10") (pintype "bidirectional"))
      (node (ref "DIP_8-15") (pin "15") (pinfunction "15_15") (pintype "bidirectional"))
    )
    (net (code "79") (name "/DIP15") (class "Default")
      (node (ref "BUS/DIP_12-15") (pin "13") (pinfunction "4B_13") (pintype "bidirectional"))
      (node (ref "DIP_8-15") (pin "16") (pinfunction "16_16") (pintype "bidirectional"))
    )
    (net (code "80") (name "/GND") (class "Default")
      (node (ref "AND_GATE") (pin "10") (pinfunction "3B_10") (pintype "bidirectional"))
      (node (ref "AND_GATE") (pin "12") (pinfunction "4A_12") (pintype "bidirectional"))
      (node (ref "AND_GATE") (pin "13") (pinfunction "4B_13") (pintype "bidirectional"))
      (node (ref "AND_GATE") (pin "7") (pinfunction "GND_7") (pintype "bidirectional"))
      (node (ref "AND_GATE") (pin "9") (pinfunction "3A_9") (pintype "bidirectional"))
      (node (ref "ARD/BRD_0-3") (pin "15") (pinfunction "~{G}_15") (pintype "bidirectional"))
      (node (ref "ARD/BRD_0-3") (pin "8") (pinfunction "GND_8") (pintype "bidirectional"))
      (node (ref "ARD/BRD_12-15") (pin "15") (pinfunction "~{G}_15") (pintype "bidirectional"))
      (node (ref "ARD/BRD_12-15") (pin "8") (pinfunction "GND_8") (pintype "bidirectional"))
      (node (ref "ARD/BRD_4-7") (pin "15") (pinfunction "~{G}_15") (pintype "bidirectional"))
      (node (ref "ARD/BRD_4-7") (pin "8") (pinfunction "GND_8") (pintype "bidirectional"))
      (node (ref "ARD/BRD_8-11") (pin "15") (pinfunction "~{G}_15") (pintype "bidirectional"))
      (node (ref "ARD/BRD_8-11") (pin "8") (pinfunction "GND_8") (pintype "bidirectional"))
      (node (ref "ARDUINO_WRITE") (pin "10") (pinfunction "3B_10") (pintype "bidirectional"))
      (node (ref "ARDUINO_WRITE") (pin "11") (pinfunction "3A_11") (pintype "bidirectional"))
      (node (ref "ARDUINO_WRITE") (pin "13") (pinfunction "4B_13") (pintype "bidirectional"))
      (node (ref "ARDUINO_WRITE") (pin "14") (pinfunction "4A_14") (pintype "bidirectional"))
      (node (ref "ARDUINO_WRITE") (pin "15") (pinfunction "~{G}_15") (pintype "bidirectional"))
      (node (ref "ARDUINO_WRITE") (pin "5") (pinfunction "2A_5") (pintype "bidirectional"))
      (node (ref "ARDUINO_WRITE") (pin "6") (pinfunction "2B_6") (pintype "bidirectional"))
      (node (ref "ARDUINO_WRITE") (pin "8") (pinfunction "GND_8") (pintype "bidirectional"))
      (node (ref "BOARD_WRITE") (pin "10") (pinfunction "3B_10") (pintype "bidirectional"))
      (node (ref "BOARD_WRITE") (pin "11") (pinfunction "3A_11") (pintype "bidirectional"))
      (node (ref "BOARD_WRITE") (pin "13") (pinfunction "4B_13") (pintype "bidirectional"))
      (node (ref "BOARD_WRITE") (pin "14") (pinfunction "4A_14") (pintype "bidirectional"))
      (node (ref "BOARD_WRITE") (pin "15") (pinfunction "~{G}_15") (pintype "bidirectional"))
      (node (ref "BOARD_WRITE") (pin "5") (pinfunction "2A_5") (pintype "bidirectional"))
      (node (ref "BOARD_WRITE") (pin "6") (pinfunction "2B_6") (pintype "bidirectional"))
      (node (ref "BOARD_WRITE") (pin "8") (pinfunction "GND_8") (pintype "bidirectional"))
      (node (ref "BUS") (pin "20") (pinfunction "20_20") (pintype "bidirectional"))
      (node (ref "BUS/DIP_0-3") (pin "15") (pinfunction "~{G}_15") (pintype "bidirectional"))
      (node (ref "BUS/DIP_0-3") (pin "8") (pinfunction "GND_8") (pintype "bidirectional"))
      (node (ref "BUS/DIP_12-15") (pin "15") (pinfunction "~{G}_15") (pintype "bidirectional"))
      (node (ref "BUS/DIP_12-15") (pin "8") (pinfunction "GND_8") (pintype "bidirectional"))
      (node (ref "BUS/DIP_4-7") (pin "15") (pinfunction "~{G}_15") (pintype "bidirectional"))
      (node (ref "BUS/DIP_4-7") (pin "8") (pinfunction "GND_8") (pintype "bidirectional"))
      (node (ref "BUS/DIP_8-11") (pin "15") (pinfunction "~{G}_15") (pintype "bidirectional"))
      (node (ref "BUS/DIP_8-11") (pin "8") (pinfunction "GND_8") (pintype "bidirectional"))
      (node (ref "C1") (pin "1") (pinfunction "1_1") (pintype "passive"))
      (node (ref "C2") (pin "1") (pinfunction "1_1") (pintype "passive"))
      (node (ref "C3") (pin "1") (pinfunction "1_1") (pintype "passive"))
      (node (ref "C4") (pin "1") (pinfunction "1_1") (pintype "passive"))
      (node (ref "LED0") (pin "K") (pinfunction "C_K") (pintype "passive"))
      (node (ref "LED1") (pin "K") (pinfunction "C_K") (pintype "passive"))
      (node (ref "LED10") (pin "K") (pinfunction "C_K") (pintype "passive"))
      (node (ref "LED11") (pin "K") (pinfunction "C_K") (pintype "passive"))
      (node (ref "LED12") (pin "K") (pinfunction "C_K") (pintype "passive"))
      (node (ref "LED13") (pin "K") (pinfunction "C_K") (pintype "passive"))
      (node (ref "LED14") (pin "K") (pinfunction "C_K") (pintype "passive"))
      (node (ref "LED15") (pin "K") (pinfunction "C_K") (pintype "passive"))
      (node (ref "LED2") (pin "K") (pinfunction "C_K") (pintype "passive"))
      (node (ref "LED3") (pin "K") (pinfunction "C_K") (pintype "passive"))
      (node (ref "LED4") (pin "K") (pinfunction "C_K") (pintype "passive"))
      (node (ref "LED5") (pin "K") (pinfunction "C_K") (pintype "passive"))
      (node (ref "LED6") (pin "K") (pinfunction "C_K") (pintype "passive"))
      (node (ref "LED7") (pin "K") (pinfunction "C_K") (pintype "passive"))
      (node (ref "LED8") (pin "K") (pinfunction "C_K") (pintype "passive"))
      (node (ref "LED9") (pin "K") (pinfunction "C_K") (pintype "passive"))
      (node (ref "MEMORY_0-7") (pin "14") (pinfunction "VSS_14") (pintype "bidirectional"))
      (node (ref "MEMORY_0-7") (pin "2") (pinfunction "A12_2") (pintype "bidirectional"))
      (node (ref "MEMORY_0-7") (pin "20") (pinfunction "CE#_20") (pintype "bidirectional"))
      (node (ref "MEMORY_8-15") (pin "14") (pinfunction "VSS_14") (pintype "bidirectional"))
      (node (ref "MEMORY_8-15") (pin "2") (pinfunction "A12_2") (pintype "bidirectional"))
      (node (ref "MEMORY_8-15") (pin "20") (pinfunction "CE#_20") (pintype "bidirectional"))
      (node (ref "RAM_OUT_0-7") (pin "10") (pinfunction "GND_10") (pintype "bidirectional"))
      (node (ref "RAM_OUT_8-15") (pin "10") (pinfunction "GND_10") (pintype "bidirectional"))
      (node (ref "S1") (pin "A3") (pinfunction "N.O._1_A3") (pintype "bidirectional"))
    )
    (net (code "81") (name "/PRGM") (class "Default")
      (node (ref "AND_GATE") (pin "1") (pinfunction "1A_1") (pintype "bidirectional"))
      (node (ref "BOARD_WRITE") (pin "1") (pinfunction "~{A}/B_1") (pintype "bidirectional"))
      (node (ref "BUS/DIP_0-3") (pin "1") (pinfunction "~{A}/B_1") (pintype "bidirectional"))
      (node (ref "BUS/DIP_12-15") (pin "1") (pinfunction "~{A}/B_1") (pintype "bidirectional"))
      (node (ref "BUS/DIP_4-7") (pin "1") (pinfunction "~{A}/B_1") (pintype "bidirectional"))
      (node (ref "BUS/DIP_8-11") (pin "1") (pinfunction "~{A}/B_1") (pintype "bidirectional"))
      (node (ref "MAR") (pin "7") (pinfunction "7_7") (pintype "bidirectional"))
    )
    (net (code "82") (name "/RAM0") (class "Default")
      (node (ref "ARD/BRD_0-3") (pin "4") (pinfunction "1Y_4") (pintype "bidirectional"))
      (node (ref "MEMORY_0-7") (pin "11") (pinfunction "DQ0_11") (pintype "bidirectional"))
      (node (ref "R0") (pin "2") (pinfunction "2_2") (pintype "passive"))
      (node (ref "RAM_OUT_0-7") (pin "2") (pinfunction "A1_2") (pintype "bidirectional"))
    )
    (net (code "83") (name "/RAM1") (class "Default")
      (node (ref "ARD/BRD_0-3") (pin "7") (pinfunction "2Y_7") (pintype "bidirectional"))
      (node (ref "MEMORY_0-7") (pin "12") (pinfunction "DQ1_12") (pintype "bidirectional"))
      (node (ref "R1") (pin "2") (pinfunction "2_2") (pintype "passive"))
      (node (ref "RAM_OUT_0-7") (pin "3") (pinfunction "A2_3") (pintype "bidirectional"))
    )
    (net (code "84") (name "/RAM2") (class "Default")
      (node (ref "ARD/BRD_0-3") (pin "9") (pinfunction "3Y_9") (pintype "bidirectional"))
      (node (ref "MEMORY_0-7") (pin "13") (pinfunction "DQ2_13") (pintype "bidirectional"))
      (node (ref "R2") (pin "2") (pinfunction "2_2") (pintype "passive"))
      (node (ref "RAM_OUT_0-7") (pin "4") (pinfunction "A3_4") (pintype "bidirectional"))
    )
    (net (code "85") (name "/RAM3") (class "Default")
      (node (ref "ARD/BRD_0-3") (pin "12") (pinfunction "4Y_12") (pintype "bidirectional"))
      (node (ref "MEMORY_0-7") (pin "15") (pinfunction "DQ3_15") (pintype "bidirectional"))
      (node (ref "R3") (pin "2") (pinfunction "2_2") (pintype "passive"))
      (node (ref "RAM_OUT_0-7") (pin "5") (pinfunction "A4_5") (pintype "bidirectional"))
    )
    (net (code "86") (name "/RAM4") (class "Default")
      (node (ref "ARD/BRD_4-7") (pin "4") (pinfunction "1Y_4") (pintype "bidirectional"))
      (node (ref "MEMORY_0-7") (pin "16") (pinfunction "DQ4_16") (pintype "bidirectional"))
      (node (ref "R4") (pin "2") (pinfunction "2_2") (pintype "passive"))
      (node (ref "RAM_OUT_0-7") (pin "6") (pinfunction "A5_6") (pintype "bidirectional"))
    )
    (net (code "87") (name "/RAM5") (class "Default")
      (node (ref "ARD/BRD_4-7") (pin "7") (pinfunction "2Y_7") (pintype "bidirectional"))
      (node (ref "MEMORY_0-7") (pin "17") (pinfunction "DQ5_17") (pintype "bidirectional"))
      (node (ref "R5") (pin "2") (pinfunction "2_2") (pintype "passive"))
      (node (ref "RAM_OUT_0-7") (pin "7") (pinfunction "A6_7") (pintype "bidirectional"))
    )
    (net (code "88") (name "/RAM6") (class "Default")
      (node (ref "ARD/BRD_4-7") (pin "9") (pinfunction "3Y_9") (pintype "bidirectional"))
      (node (ref "MEMORY_0-7") (pin "18") (pinfunction "DQ6_18") (pintype "bidirectional"))
      (node (ref "R6") (pin "2") (pinfunction "2_2") (pintype "passive"))
      (node (ref "RAM_OUT_0-7") (pin "8") (pinfunction "A7_8") (pintype "bidirectional"))
    )
    (net (code "89") (name "/RAM7") (class "Default")
      (node (ref "ARD/BRD_4-7") (pin "12") (pinfunction "4Y_12") (pintype "bidirectional"))
      (node (ref "MEMORY_0-7") (pin "19") (pinfunction "DQ7_19") (pintype "bidirectional"))
      (node (ref "R7") (pin "2") (pinfunction "2_2") (pintype "passive"))
      (node (ref "RAM_OUT_0-7") (pin "9") (pinfunction "A8_9") (pintype "bidirectional"))
    )
    (net (code "90") (name "/RAM8") (class "Default")
      (node (ref "ARD/BRD_8-11") (pin "4") (pinfunction "1Y_4") (pintype "bidirectional"))
      (node (ref "MEMORY_8-15") (pin "11") (pinfunction "DQ0_11") (pintype "bidirectional"))
      (node (ref "R8") (pin "2") (pinfunction "2_2") (pintype "passive"))
      (node (ref "RAM_OUT_8-15") (pin "2") (pinfunction "A1_2") (pintype "bidirectional"))
    )
    (net (code "91") (name "/RAM9") (class "Default")
      (node (ref "ARD/BRD_8-11") (pin "7") (pinfunction "2Y_7") (pintype "bidirectional"))
      (node (ref "MEMORY_8-15") (pin "12") (pinfunction "DQ1_12") (pintype "bidirectional"))
      (node (ref "R9") (pin "2") (pinfunction "2_2") (pintype "passive"))
      (node (ref "RAM_OUT_8-15") (pin "3") (pinfunction "A2_3") (pintype "bidirectional"))
    )
    (net (code "92") (name "/RAM10") (class "Default")
      (node (ref "ARD/BRD_8-11") (pin "9") (pinfunction "3Y_9") (pintype "bidirectional"))
      (node (ref "MEMORY_8-15") (pin "13") (pinfunction "DQ2_13") (pintype "bidirectional"))
      (node (ref "R10") (pin "2") (pinfunction "2_2") (pintype "passive"))
      (node (ref "RAM_OUT_8-15") (pin "4") (pinfunction "A3_4") (pintype "bidirectional"))
    )
    (net (code "93") (name "/RAM11") (class "Default")
      (node (ref "ARD/BRD_8-11") (pin "12") (pinfunction "4Y_12") (pintype "bidirectional"))
      (node (ref "MEMORY_8-15") (pin "15") (pinfunction "DQ3_15") (pintype "bidirectional"))
      (node (ref "R11") (pin "2") (pinfunction "2_2") (pintype "passive"))
      (node (ref "RAM_OUT_8-15") (pin "5") (pinfunction "A4_5") (pintype "bidirectional"))
    )
    (net (code "94") (name "/RAM12") (class "Default")
      (node (ref "ARD/BRD_12-15") (pin "4") (pinfunction "1Y_4") (pintype "bidirectional"))
      (node (ref "MEMORY_8-15") (pin "16") (pinfunction "DQ4_16") (pintype "bidirectional"))
      (node (ref "R12") (pin "2") (pinfunction "2_2") (pintype "passive"))
      (node (ref "RAM_OUT_8-15") (pin "6") (pinfunction "A5_6") (pintype "bidirectional"))
    )
    (net (code "95") (name "/RAM13") (class "Default")
      (node (ref "ARD/BRD_12-15") (pin "7") (pinfunction "2Y_7") (pintype "bidirectional"))
      (node (ref "MEMORY_8-15") (pin "17") (pinfunction "DQ5_17") (pintype "bidirectional"))
      (node (ref "R13") (pin "2") (pinfunction "2_2") (pintype "passive"))
      (node (ref "RAM_OUT_8-15") (pin "7") (pinfunction "A6_7") (pintype "bidirectional"))
    )
    (net (code "96") (name "/RAM14") (class "Default")
      (node (ref "ARD/BRD_12-15") (pin "9") (pinfunction "3Y_9") (pintype "bidirectional"))
      (node (ref "MEMORY_8-15") (pin "18") (pinfunction "DQ6_18") (pintype "bidirectional"))
      (node (ref "R14") (pin "2") (pinfunction "2_2") (pintype "passive"))
      (node (ref "RAM_OUT_8-15") (pin "8") (pinfunction "A7_8") (pintype "bidirectional"))
    )
    (net (code "97") (name "/RAM15") (class "Default")
      (node (ref "ARD/BRD_12-15") (pin "12") (pinfunction "4Y_12") (pintype "bidirectional"))
      (node (ref "MEMORY_8-15") (pin "19") (pinfunction "DQ7_19") (pintype "bidirectional"))
      (node (ref "R15") (pin "2") (pinfunction "2_2") (pintype "passive"))
      (node (ref "RAM_OUT_8-15") (pin "9") (pinfunction "A8_9") (pintype "bidirectional"))
    )
    (net (code "98") (name "/RAMPROG") (class "Default")
      (node (ref "AND_GATE") (pin "3") (pinfunction "1Y_3") (pintype "bidirectional"))
      (node (ref "ARD/BRD_0-3") (pin "1") (pinfunction "~{A}/B_1") (pintype "bidirectional"))
      (node (ref "ARD/BRD_12-15") (pin "1") (pinfunction "~{A}/B_1") (pintype "bidirectional"))
      (node (ref "ARD/BRD_4-7") (pin "1") (pinfunction "~{A}/B_1") (pintype "bidirectional"))
      (node (ref "ARD/BRD_8-11") (pin "1") (pinfunction "~{A}/B_1") (pintype "bidirectional"))
    )
    (net (code "99") (name "/RI") (class "Default")
      (node (ref "AND_GATE") (pin "5") (pinfunction "2B_5") (pintype "bidirectional"))
      (node (ref "BUS") (pin "18") (pinfunction "18_18") (pintype "bidirectional"))
    )
    (net (code "100") (name "/RO") (class "Default")
      (node (ref "BUS") (pin "17") (pinfunction "17_17") (pintype "bidirectional"))
      (node (ref "MEMORY_0-7") (pin "22") (pinfunction "OE#_22") (pintype "bidirectional"))
      (node (ref "MEMORY_8-15") (pin "22") (pinfunction "OE#_22") (pintype "bidirectional"))
      (node (ref "RAM_OUT_0-7") (pin "1") (pinfunction "~{OE1}_1") (pintype "bidirectional"))
      (node (ref "RAM_OUT_0-7") (pin "19") (pinfunction "~{OE2}_19") (pintype "bidirectional"))
      (node (ref "RAM_OUT_8-15") (pin "1") (pinfunction "~{OE1}_1") (pintype "bidirectional"))
      (node (ref "RAM_OUT_8-15") (pin "19") (pinfunction "~{OE2}_19") (pintype "bidirectional"))
    )
    (net (code "101") (name "/VCC") (class "Default")
      (node (ref "AND_GATE") (pin "14") (pinfunction "VCC_14") (pintype "bidirectional"))
      (node (ref "ARD/BRD_0-3") (pin "16") (pinfunction "VCC_16") (pintype "bidirectional"))
      (node (ref "ARD/BRD_12-15") (pin "16") (pinfunction "VCC_16") (pintype "bidirectional"))
      (node (ref "ARD/BRD_4-7") (pin "16") (pinfunction "VCC_16") (pintype "bidirectional"))
      (node (ref "ARD/BRD_8-11") (pin "16") (pinfunction "VCC_16") (pintype "bidirectional"))
      (node (ref "ARDUINO_WRITE") (pin "16") (pinfunction "VCC_16") (pintype "bidirectional"))
      (node (ref "BOARD_WRITE") (pin "16") (pinfunction "VCC_16") (pintype "bidirectional"))
      (node (ref "BUS") (pin "19") (pinfunction "19_19") (pintype "bidirectional"))
      (node (ref "BUS/DIP_0-3") (pin "16") (pinfunction "VCC_16") (pintype "bidirectional"))
      (node (ref "BUS/DIP_12-15") (pin "16") (pinfunction "VCC_16") (pintype "bidirectional"))
      (node (ref "BUS/DIP_4-7") (pin "16") (pinfunction "VCC_16") (pintype "bidirectional"))
      (node (ref "BUS/DIP_8-11") (pin "16") (pinfunction "VCC_16") (pintype "bidirectional"))
      (node (ref "C1") (pin "2") (pinfunction "2_2") (pintype "passive"))
      (node (ref "C2") (pin "2") (pinfunction "2_2") (pintype "passive"))
      (node (ref "C3") (pin "2") (pinfunction "2_2") (pintype "passive"))
      (node (ref "C4") (pin "2") (pinfunction "2_2") (pintype "passive"))
      (node (ref "DIP_0-7") (pin "1") (pinfunction "1_1") (pintype "bidirectional"))
      (node (ref "DIP_0-7") (pin "2") (pinfunction "2_2") (pintype "bidirectional"))
      (node (ref "DIP_0-7") (pin "3") (pinfunction "3_3") (pintype "bidirectional"))
      (node (ref "DIP_0-7") (pin "4") (pinfunction "4_4") (pintype "bidirectional"))
      (node (ref "DIP_0-7") (pin "5") (pinfunction "5_5") (pintype "bidirectional"))
      (node (ref "DIP_0-7") (pin "6") (pinfunction "6_6") (pintype "bidirectional"))
      (node (ref "DIP_0-7") (pin "7") (pinfunction "7_7") (pintype "bidirectional"))
      (node (ref "DIP_0-7") (pin "8") (pinfunction "8_8") (pintype "bidirectional"))
      (node (ref "DIP_8-15") (pin "1") (pinfunction "1_1") (pintype "bidirectional"))
      (node (ref "DIP_8-15") (pin "2") (pinfunction "2_2") (pintype "bidirectional"))
      (node (ref "DIP_8-15") (pin "3") (pinfunction "3_3") (pintype "bidirectional"))
      (node (ref "DIP_8-15") (pin "4") (pinfunction "4_4") (pintype "bidirectional"))
      (node (ref "DIP_8-15") (pin "5") (pinfunction "5_5") (pintype "bidirectional"))
      (node (ref "DIP_8-15") (pin "6") (pinfunction "6_6") (pintype "bidirectional"))
      (node (ref "DIP_8-15") (pin "7") (pinfunction "7_7") (pintype "bidirectional"))
      (node (ref "DIP_8-15") (pin "8") (pinfunction "8_8") (pintype "bidirectional"))
      (node (ref "MEMORY_0-7") (pin "26") (pinfunction "CE2_26") (pintype "bidirectional"))
      (node (ref "MEMORY_0-7") (pin "28") (pinfunction "VCC_28") (pintype "bidirectional"))
      (node (ref "MEMORY_8-15") (pin "26") (pinfunction "CE2_26") (pintype "bidirectional"))
      (node (ref "MEMORY_8-15") (pin "28") (pinfunction "VCC_28") (pintype "bidirectional"))
      (node (ref "RAM_OUT_0-7") (pin "20") (pinfunction "VCC_20") (pintype "bidirectional"))
      (node (ref "RAM_OUT_8-15") (pin "20") (pinfunction "VCC_20") (pintype "bidirectional"))
      (node (ref "S1") (pin "A1") (pinfunction "N.C._1_A1") (pintype "bidirectional"))
    )
    (net (code "102") (name "/WE") (class "Default")
      (node (ref "ARDUINO_WRITE") (pin "4") (pinfunction "1Y_4") (pintype "bidirectional"))
      (node (ref "MEMORY_0-7") (pin "27") (pinfunction "WE#_27") (pintype "bidirectional"))
      (node (ref "MEMORY_8-15") (pin "27") (pinfunction "WE#_27") (pintype "bidirectional"))
    )
    (net (code "103") (name "Net-(AND_GATE-2Y)") (class "Default")
      (node (ref "AND_GATE") (pin "6") (pinfunction "2Y_6") (pintype "bidirectional"))
      (node (ref "BOARD_WRITE") (pin "2") (pinfunction "1A_2") (pintype "bidirectional"))
    )
    (net (code "104") (name "Net-(ARDUINO_WRITE-1A)") (class "Default")
      (node (ref "ARDUINO_WRITE") (pin "2") (pinfunction "1A_2") (pintype "bidirectional"))
      (node (ref "BOARD_WRITE") (pin "4") (pinfunction "1Y_4") (pintype "bidirectional"))
    )
    (net (code "105") (name "Net-(BOARD_WRITE-1B)") (class "Default")
      (node (ref "BOARD_WRITE") (pin "3") (pinfunction "1B_3") (pintype "bidirectional"))
      (node (ref "S1") (pin "A2") (pinfunction "COM_1_A2") (pintype "bidirectional"))
    )
    (net (code "106") (name "Net-(LED0-PadA)") (class "Default")
      (node (ref "LED0") (pin "A") (pinfunction "A_A") (pintype "passive"))
      (node (ref "R0") (pin "1") (pinfunction "1_1") (pintype "passive"))
    )
    (net (code "107") (name "Net-(LED1-PadA)") (class "Default")
      (node (ref "LED1") (pin "A") (pinfunction "A_A") (pintype "passive"))
      (node (ref "R1") (pin "1") (pinfunction "1_1") (pintype "passive"))
    )
    (net (code "108") (name "Net-(LED2-PadA)") (class "Default")
      (node (ref "LED2") (pin "A") (pinfunction "A_A") (pintype "passive"))
      (node (ref "R2") (pin "1") (pinfunction "1_1") (pintype "passive"))
    )
    (net (code "109") (name "Net-(LED3-PadA)") (class "Default")
      (node (ref "LED3") (pin "A") (pinfunction "A_A") (pintype "passive"))
      (node (ref "R3") (pin "1") (pinfunction "1_1") (pintype "passive"))
    )
    (net (code "110") (name "Net-(LED4-PadA)") (class "Default")
      (node (ref "LED4") (pin "A") (pinfunction "A_A") (pintype "passive"))
      (node (ref "R4") (pin "1") (pinfunction "1_1") (pintype "passive"))
    )
    (net (code "111") (name "Net-(LED5-PadA)") (class "Default")
      (node (ref "LED5") (pin "A") (pinfunction "A_A") (pintype "passive"))
      (node (ref "R5") (pin "1") (pinfunction "1_1") (pintype "passive"))
    )
    (net (code "112") (name "Net-(LED6-PadA)") (class "Default")
      (node (ref "LED6") (pin "A") (pinfunction "A_A") (pintype "passive"))
      (node (ref "R6") (pin "1") (pinfunction "1_1") (pintype "passive"))
    )
    (net (code "113") (name "Net-(LED7-PadA)") (class "Default")
      (node (ref "LED7") (pin "A") (pinfunction "A_A") (pintype "passive"))
      (node (ref "R7") (pin "1") (pinfunction "1_1") (pintype "passive"))
    )
    (net (code "114") (name "Net-(LED8-PadA)") (class "Default")
      (node (ref "LED8") (pin "A") (pinfunction "A_A") (pintype "passive"))
      (node (ref "R8") (pin "1") (pinfunction "1_1") (pintype "passive"))
    )
    (net (code "115") (name "Net-(LED9-PadA)") (class "Default")
      (node (ref "LED9") (pin "A") (pinfunction "A_A") (pintype "passive"))
      (node (ref "R9") (pin "1") (pinfunction "1_1") (pintype "passive"))
    )
    (net (code "116") (name "Net-(LED10-PadA)") (class "Default")
      (node (ref "LED10") (pin "A") (pinfunction "A_A") (pintype "passive"))
      (node (ref "R10") (pin "1") (pinfunction "1_1") (pintype "passive"))
    )
    (net (code "117") (name "Net-(LED11-PadA)") (class "Default")
      (node (ref "LED11") (pin "A") (pinfunction "A_A") (pintype "passive"))
      (node (ref "R11") (pin "1") (pinfunction "1_1") (pintype "passive"))
    )
    (net (code "118") (name "Net-(LED12-PadA)") (class "Default")
      (node (ref "LED12") (pin "A") (pinfunction "A_A") (pintype "passive"))
      (node (ref "R12") (pin "1") (pinfunction "1_1") (pintype "passive"))
    )
    (net (code "119") (name "Net-(LED13-PadA)") (class "Default")
      (node (ref "LED13") (pin "A") (pinfunction "A_A") (pintype "passive"))
      (node (ref "R13") (pin "1") (pinfunction "1_1") (pintype "passive"))
    )
    (net (code "120") (name "Net-(LED14-PadA)") (class "Default")
      (node (ref "LED14") (pin "A") (pinfunction "A_A") (pintype "passive"))
      (node (ref "R14") (pin "1") (pinfunction "1_1") (pintype "passive"))
    )
    (net (code "121") (name "Net-(LED15-PadA)") (class "Default")
      (node (ref "LED15") (pin "A") (pinfunction "A_A") (pintype "passive"))
      (node (ref "R15") (pin "1") (pinfunction "1_1") (pintype "passive"))
    )
    (net (code "122") (name "unconnected-(AND_GATE-3Y-Pad8)") (class "Default")
      (node (ref "AND_GATE") (pin "8") (pinfunction "3Y_8") (pintype "bidirectional"))
    )
    (net (code "123") (name "unconnected-(AND_GATE-4Y-Pad11)") (class "Default")
      (node (ref "AND_GATE") (pin "11") (pinfunction "4Y_11") (pintype "bidirectional"))
    )
    (net (code "124") (name "unconnected-(ARDUINO_WRITE-2Y-Pad7)") (class "Default")
      (node (ref "ARDUINO_WRITE") (pin "7") (pinfunction "2Y_7") (pintype "bidirectional"))
    )
    (net (code "125") (name "unconnected-(ARDUINO_WRITE-3Y-Pad9)") (class "Default")
      (node (ref "ARDUINO_WRITE") (pin "9") (pinfunction "3Y_9") (pintype "bidirectional"))
    )
    (net (code "126") (name "unconnected-(ARDUINO_WRITE-4Y-Pad12)") (class "Default")
      (node (ref "ARDUINO_WRITE") (pin "12") (pinfunction "4Y_12") (pintype "bidirectional"))
    )
    (net (code "127") (name "unconnected-(BOARD_WRITE-2Y-Pad7)") (class "Default")
      (node (ref "BOARD_WRITE") (pin "7") (pinfunction "2Y_7") (pintype "bidirectional"))
    )
    (net (code "128") (name "unconnected-(BOARD_WRITE-3Y-Pad9)") (class "Default")
      (node (ref "BOARD_WRITE") (pin "9") (pinfunction "3Y_9") (pintype "bidirectional"))
    )
    (net (code "129") (name "unconnected-(BOARD_WRITE-4Y-Pad12)") (class "Default")
      (node (ref "BOARD_WRITE") (pin "12") (pinfunction "4Y_12") (pintype "bidirectional"))
    )
    (net (code "130") (name "unconnected-(BUS-Pad22)") (class "Default")
      (node (ref "BUS") (pin "22") (pinfunction "22_22") (pintype "bidirectional"))
    )
    (net (code "131") (name "unconnected-(BUS-Pad23)") (class "Default")
      (node (ref "BUS") (pin "23") (pinfunction "23_23") (pintype "bidirectional"))
    )
    (net (code "132") (name "unconnected-(BUS-Pad24)") (class "Default")
      (node (ref "BUS") (pin "24") (pinfunction "24_24") (pintype "bidirectional"))
    )
    (net (code "133") (name "unconnected-(MAR-Pad14)") (class "Default")
      (node (ref "MAR") (pin "14") (pinfunction "14_14") (pintype "bidirectional"))
    )
    (net (code "134") (name "unconnected-(MEMORY_0-7-NC-Pad1)") (class "Default")
      (node (ref "MEMORY_0-7") (pin "1") (pinfunction "NC_1") (pintype "no_connect"))
    )
    (net (code "135") (name "unconnected-(MEMORY_8-15-NC-Pad1)") (class "Default")
      (node (ref "MEMORY_8-15") (pin "1") (pinfunction "NC_1") (pintype "no_connect"))
    )
    (net (code "136") (name "unconnected-(S1-COM_2-PadB2)") (class "Default")
      (node (ref "S1") (pin "B2") (pinfunction "COM_2_B2") (pintype "bidirectional"))
    )
    (net (code "137") (name "unconnected-(S1-N.C._2-PadB1)") (class "Default")
      (node (ref "S1") (pin "B1") (pinfunction "N.C._2_B1") (pintype "bidirectional"))
    )
    (net (code "138") (name "unconnected-(S1-N.O._2-PadB3)") (class "Default")
      (node (ref "S1") (pin "B3") (pinfunction "N.O._2_B3") (pintype "bidirectional"))
    )
  )
)
